# Sheet2.net
KiCad netlist of a schematic drawn in Altium Designer
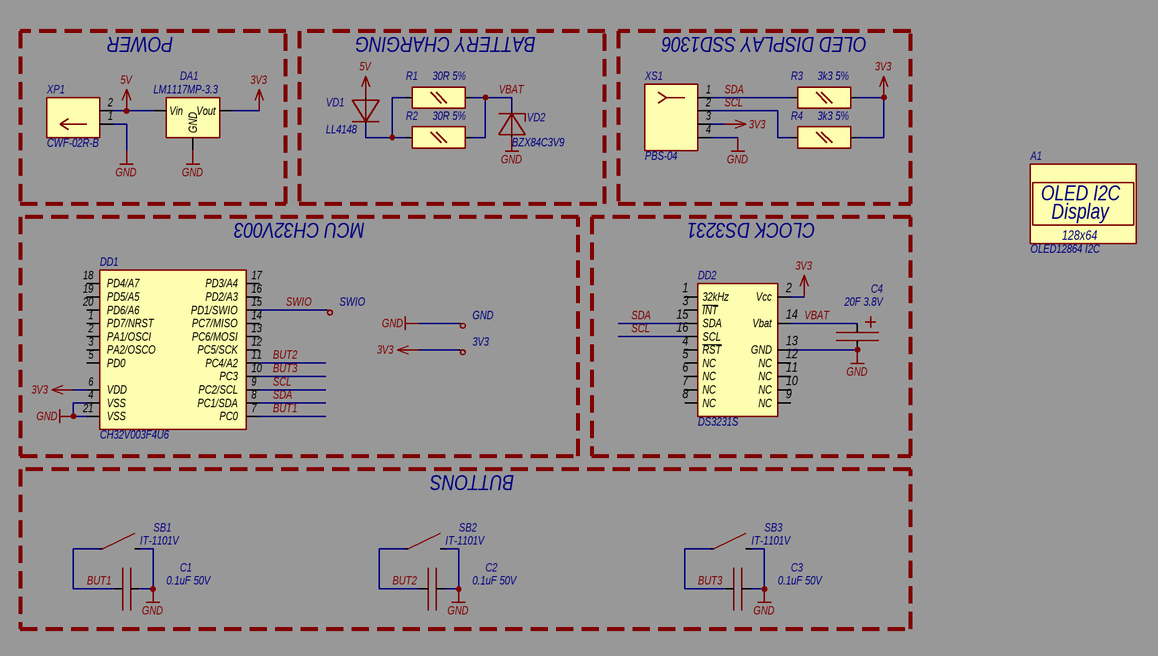
[diagram p0: Sheet2.SchDoc]

(export (version "E")
  (design (tool "Eeschema 10.0.6"))
  (components
    (comp (ref "A1")
      (value "OLED12864 I2C")
      (footprint "OLED12864 I2C connector")
      (fields (field (name "PART NUMBER") "OLED12864 I2C connector"))
      (libsource (lib "ATwiceDB") (part "OLED12864 I2C connector"))
    )
    (comp (ref "C1")
      (value "0.1uF 50V")
      (footprint "CAP SMD0805")
      (description "Конденсатор керамический SMD 0805 0.1uF 50V ±20%")
      (fields (field (name "PART NUMBER") "Cap 0805 0.1uF 50V"))
      (libsource (lib "ATwiceDB") (part "Cap"))
    )
    (comp (ref "C2")
      (value "0.1uF 50V")
      (footprint "CAP SMD0805")
      (description "Конденсатор керамический SMD 0805 0.1uF 50V ±20%")
      (fields (field (name "PART NUMBER") "Cap 0805 0.1uF 50V"))
      (libsource (lib "ATwiceDB") (part "Cap"))
    )
    (comp (ref "C3")
      (value "0.1uF 50V")
      (footprint "CAP SMD0805")
      (description "Конденсатор керамический SMD 0805 0.1uF 50V ±20%")
      (fields (field (name "PART NUMBER") "Cap 0805 0.1uF 50V"))
      (libsource (lib "ATwiceDB") (part "Cap"))
    )
    (comp (ref "C4")
      (value "20F 3.8V")
      (footprint "LIC0813LAYDOWN")
      (description "Ионистор 20F 3.8V 0813")
      (fields (field (name "PART NUMBER") "LIC 0813 206"))
      (libsource (lib "ATwiceDB") (part "Cap_plus"))
    )
    (comp (ref "DA1")
      (value "LM1117MP-3.3")
      (footprint "SOT223")
      (description "LDO стабилизатор")
      (libsource (lib "ATwiceDB") (part "LM1117"))
    )
    (comp (ref "DD1")
      (value "CH32V003F4U6")
      (footprint "QFN20_3X3_0.4")
      (description "Микроконтроллер CH32V003F4U6 QFN20 -40 +85")
      (libsource (lib "ATwiceDB") (part "CH32V003F4U6"))
    )
    (comp (ref "DD2")
      (value "DS3231S")
      (footprint "SO16W")
      (description "Микросхема DS3231S SO16W часы реального времени")
      (libsource (lib "ATwiceDB") (part "DS3231"))
    )
    (comp (ref "R1")
      (value "30R 5%")
      (footprint "SMD 0805")
      (description "Резистор SMD 0805 30R 5%")
      (fields (field (name "PART NUMBER") "Res 0805 30R 5%"))
      (libsource (lib "ATwiceDB") (part "Res_0125"))
    )
    (comp (ref "R2")
      (value "30R 5%")
      (footprint "SMD 0805")
      (description "Резистор SMD 0805 30R 5%")
      (fields (field (name "PART NUMBER") "Res 0805 30R 5%"))
      (libsource (lib "ATwiceDB") (part "Res_0125"))
    )
    (comp (ref "R3")
      (value "3k3 5%")
      (footprint "SMD 0805")
      (description "Резистор SMD 0805 3k3 5%")
      (fields (field (name "PART NUMBER") "Res 0805 3k3 5%"))
      (libsource (lib "ATwiceDB") (part "Res_0125"))
    )
    (comp (ref "R4")
      (value "3k3 5%")
      (footprint "SMD 0805")
      (description "Резистор SMD 0805 3k3 5%")
      (fields (field (name "PART NUMBER") "Res 0805 3k3 5%"))
      (libsource (lib "ATwiceDB") (part "Res_0125"))
    )
    (comp (ref "SB1")
      (value "IT-1101V")
      (footprint "IT-1101V_NO_SHIELD")
      (description "Кнопка тактовая IT-1101V угловая без рамки")
      (fields (field (name "PART NUMBER") "IT-1101V_no_shield"))
      (libsource (lib "ATwiceDB") (part "SB"))
    )
    (comp (ref "SB2")
      (value "IT-1101V")
      (footprint "IT-1101V_NO_SHIELD")
      (description "Кнопка тактовая IT-1101V угловая без рамки")
      (fields (field (name "PART NUMBER") "IT-1101V_no_shield"))
      (libsource (lib "ATwiceDB") (part "SB"))
    )
    (comp (ref "SB3")
      (value "IT-1101V")
      (footprint "IT-1101V_NO_SHIELD")
      (description "Кнопка тактовая IT-1101V угловая без рамки")
      (fields (field (name "PART NUMBER") "IT-1101V_no_shield"))
      (libsource (lib "ATwiceDB") (part "SB"))
    )
    (comp (ref "VD1")
      (value "LL4148")
      (footprint "MINIMELF")
      (description "Диод LL4148")
      (libsource (lib "ATwiceDB") (part "Diode"))
    )
    (comp (ref "VD2")
      (value "BZX84C3V9")
      (footprint "SOT23_1A3C")
      (description "Стабилитрон BZX84C3V9 SOT23")
      (libsource (lib "ATwiceDB") (part "Stab"))
    )
    (comp (ref "XP1")
      (value "CWF-02R-B")
      (footprint "CWF-02R-B")
      (description "Разъём CWF-02R-B вилка угловая 2,50мм тип B")
      (libsource (lib "ATwiceDB") (part "Conn_XP02"))
    )
    (comp (ref "XS1")
      (value "PBS-04")
      (footprint "PBS-04")
      (description "Разъём PBS-04 гнездо однорядное 2,54мм")
      (libsource (lib "ATwiceDB") (part "Conn_XS04"))
    )
    (comp (ref "XX1")
      (value "SWIO")
      (footprint "SMD_Pad")
      (fields (field (name "PART NUMBER") "SMD Pad"))
      (libsource (lib "ATwiceDB") (part "TestPoint"))
    )
    (comp (ref "XX2")
      (value "GND")
      (footprint "SMD_Pad")
      (fields (field (name "PART NUMBER") "SMD Pad"))
      (libsource (lib "ATwiceDB") (part "TestPoint"))
    )
    (comp (ref "XX3")
      (value "3V3")
      (footprint "SMD_Pad")
      (fields (field (name "PART NUMBER") "SMD Pad"))
      (libsource (lib "ATwiceDB") (part "TestPoint"))
    )
  )
  (nets
    (net (code "1") (name "/BUT1") (class "Default")
      (node (ref "C1") (pin "1") (pinfunction "1_1") (pintype "passive"))
      (node (ref "DD1") (pin "7") (pinfunction "PC0_7") (pintype "passive"))
      (node (ref "SB1") (pin "1") (pinfunction "1_1") (pintype "passive"))
    )
    (net (code "2") (name "/BUT2") (class "Default")
      (node (ref "C2") (pin "1") (pinfunction "1_1") (pintype "passive"))
      (node (ref "DD1") (pin "11") (pinfunction "PC4/A2_11") (pintype "passive"))
      (node (ref "SB2") (pin "1") (pinfunction "1_1") (pintype "passive"))
    )
    (net (code "3") (name "/BUT3") (class "Default")
      (node (ref "C3") (pin "1") (pinfunction "1_1") (pintype "passive"))
      (node (ref "DD1") (pin "10") (pinfunction "PC3_10") (pintype "passive"))
      (node (ref "SB3") (pin "1") (pinfunction "1_1") (pintype "passive"))
    )
    (net (code "4") (name "/SCL") (class "Default")
      (node (ref "DD1") (pin "9") (pinfunction "PC2/SCL_9") (pintype "passive"))
      (node (ref "DD2") (pin "16") (pinfunction "SCL_16") (pintype "passive"))
      (node (ref "R4") (pin "1") (pinfunction "1_1") (pintype "passive"))
      (node (ref "XS1") (pin "2") (pintype "passive"))
    )
    (net (code "5") (name "/SDA") (class "Default")
      (node (ref "DD1") (pin "8") (pinfunction "PC1/SDA_8") (pintype "passive"))
      (node (ref "DD2") (pin "15") (pinfunction "SDA_15") (pintype "passive"))
      (node (ref "R3") (pin "1") (pinfunction "1_1") (pintype "passive"))
      (node (ref "XS1") (pin "1") (pintype "passive"))
    )
    (net (code "6") (name "/SWIO") (class "Default")
      (node (ref "DD1") (pin "15") (pinfunction "PD1/SWIO_15") (pintype "passive"))
      (node (ref "XX1") (pin "1") (pinfunction "Name_1") (pintype "passive"))
    )
    (net (code "7") (name "/VBAT") (class "Default")
      (node (ref "C4") (pin "1") (pinfunction "1_1") (pintype "passive"))
      (node (ref "DD2") (pin "14") (pinfunction "Vbat_14") (pintype "passive"))
      (node (ref "R1") (pin "2") (pinfunction "2_2") (pintype "passive"))
      (node (ref "R2") (pin "2") (pinfunction "2_2") (pintype "passive"))
      (node (ref "VD2") (pin "C") (pinfunction "C_C") (pintype "passive"))
    )
    (net (code "8") (name "3V3") (class "Default")
      (node (ref "DA1") (pin "2") (pinfunction "Vout_2") (pintype "passive"))
      (node (ref "DD1") (pin "6") (pinfunction "VDD_6") (pintype "passive"))
      (node (ref "DD2") (pin "2") (pinfunction "Vcc_2") (pintype "passive"))
      (node (ref "R3") (pin "2") (pinfunction "2_2") (pintype "passive"))
      (node (ref "R4") (pin "2") (pinfunction "2_2") (pintype "passive"))
      (node (ref "XS1") (pin "3") (pintype "passive"))
      (node (ref "XX3") (pin "1") (pinfunction "Name_1") (pintype "passive"))
    )
    (net (code "9") (name "5V") (class "Default")
      (node (ref "DA1") (pin "3") (pinfunction "Vin_3") (pintype "passive"))
      (node (ref "VD1") (pin "A") (pinfunction "A_A") (pintype "passive"))
      (node (ref "XP1") (pin "2") (pintype "passive"))
    )
    (net (code "10") (name "GND") (class "Default")
      (node (ref "C1") (pin "2") (pinfunction "2_2") (pintype "passive"))
      (node (ref "C2") (pin "2") (pinfunction "2_2") (pintype "passive"))
      (node (ref "C3") (pin "2") (pinfunction "2_2") (pintype "passive"))
      (node (ref "C4") (pin "2") (pinfunction "2_2") (pintype "passive"))
      (node (ref "DA1") (pin "1") (pinfunction "GND_1") (pintype "passive"))
      (node (ref "DD1") (pin "21") (pinfunction "VSS_21") (pintype "passive"))
      (node (ref "DD1") (pin "4") (pinfunction "VSS_4") (pintype "passive"))
      (node (ref "DD2") (pin "13") (pinfunction "GND_13") (pintype "passive"))
      (node (ref "SB1") (pin "2") (pinfunction "2_2") (pintype "passive"))
      (node (ref "SB2") (pin "2") (pinfunction "2_2") (pintype "passive"))
      (node (ref "SB3") (pin "2") (pinfunction "2_2") (pintype "passive"))
      (node (ref "VD2") (pin "A") (pinfunction "A_A") (pintype "passive"))
      (node (ref "XP1") (pin "1") (pintype "passive"))
      (node (ref "XS1") (pin "4") (pintype "passive"))
      (node (ref "XX2") (pin "1") (pinfunction "Name_1") (pintype "passive"))
    )
    (net (code "11") (name "Net-(R1-Pad1)") (class "Default")
      (node (ref "R1") (pin "1") (pinfunction "1_1") (pintype "passive"))
      (node (ref "R2") (pin "1") (pinfunction "1_1") (pintype "passive"))
      (node (ref "VD1") (pin "C") (pinfunction "C_C") (pintype "passive"))
    )
    (net (code "12") (name "unconnected-(DD1-PA1{slash}OSCI-Pad2)") (class "Default")
      (node (ref "DD1") (pin "2") (pinfunction "PA1/OSCI_2") (pintype "passive"))
    )
    (net (code "13") (name "unconnected-(DD1-PA2{slash}OSCO-Pad3)") (class "Default")
      (node (ref "DD1") (pin "3") (pinfunction "PA2/OSCO_3") (pintype "passive"))
    )
    (net (code "14") (name "unconnected-(DD1-PC5{slash}SCK-Pad12)") (class "Default")
      (node (ref "DD1") (pin "12") (pinfunction "PC5/SCK_12") (pintype "passive"))
    )
    (net (code "15") (name "unconnected-(DD1-PC6{slash}MOSI-Pad13)") (class "Default")
      (node (ref "DD1") (pin "13") (pinfunction "PC6/MOSI_13") (pintype "passive"))
    )
    (net (code "16") (name "unconnected-(DD1-PC7{slash}MISO-Pad14)") (class "Default")
      (node (ref "DD1") (pin "14") (pinfunction "PC7/MISO_14") (pintype "passive"))
    )
    (net (code "17") (name "unconnected-(DD1-PD0-Pad5)") (class "Default")
      (node (ref "DD1") (pin "5") (pinfunction "PD0_5") (pintype "passive"))
    )
    (net (code "18") (name "unconnected-(DD1-PD2{slash}A3-Pad16)") (class "Default")
      (node (ref "DD1") (pin "16") (pinfunction "PD2/A3_16") (pintype "passive"))
    )
    (net (code "19") (name "unconnected-(DD1-PD3{slash}A4-Pad17)") (class "Default")
      (node (ref "DD1") (pin "17") (pinfunction "PD3/A4_17") (pintype "passive"))
    )
    (net (code "20") (name "unconnected-(DD1-PD4{slash}A7-Pad18)") (class "Default")
      (node (ref "DD1") (pin "18") (pinfunction "PD4/A7_18") (pintype "passive"))
    )
    (net (code "21") (name "unconnected-(DD1-PD5{slash}A5-Pad19)") (class "Default")
      (node (ref "DD1") (pin "19") (pinfunction "PD5/A5_19") (pintype "passive"))
    )
    (net (code "22") (name "unconnected-(DD1-PD6{slash}A6-Pad20)") (class "Default")
      (node (ref "DD1") (pin "20") (pinfunction "PD6/A6_20") (pintype "passive"))
    )
    (net (code "23") (name "unconnected-(DD1-PD7{slash}NRST-Pad1)") (class "Default")
      (node (ref "DD1") (pin "1") (pinfunction "PD7/NRST_1") (pintype "passive"))
    )
    (net (code "24") (name "unconnected-(DD2-32kHz-Pad1)") (class "Default")
      (node (ref "DD2") (pin "1") (pinfunction "32kHz_1") (pintype "passive"))
    )
    (net (code "25") (name "unconnected-(DD2-NC-Pad5)") (class "Default")
      (node (ref "DD2") (pin "5") (pinfunction "NC_5") (pintype "passive"))
    )
    (net (code "26") (name "unconnected-(DD2-NC-Pad6)") (class "Default")
      (node (ref "DD2") (pin "6") (pinfunction "NC_6") (pintype "passive"))
    )
    (net (code "27") (name "unconnected-(DD2-NC-Pad7)") (class "Default")
      (node (ref "DD2") (pin "7") (pinfunction "NC_7") (pintype "passive"))
    )
    (net (code "28") (name "unconnected-(DD2-NC-Pad8)") (class "Default")
      (node (ref "DD2") (pin "8") (pinfunction "NC_8") (pintype "passive"))
    )
    (net (code "29") (name "unconnected-(DD2-NC-Pad9)") (class "Default")
      (node (ref "DD2") (pin "9") (pinfunction "NC_9") (pintype "passive"))
    )
    (net (code "30") (name "unconnected-(DD2-NC-Pad10)") (class "Default")
      (node (ref "DD2") (pin "10") (pinfunction "NC_10") (pintype "passive"))
    )
    (net (code "31") (name "unconnected-(DD2-NC-Pad11)") (class "Default")
      (node (ref "DD2") (pin "11") (pinfunction "NC_11") (pintype "passive"))
    )
    (net (code "32") (name "unconnected-(DD2-NC-Pad12)") (class "Default")
      (node (ref "DD2") (pin "12") (pinfunction "NC_12") (pintype "passive"))
    )
    (net (code "33") (name "unconnected-(DD2-~{INT}-Pad3)") (class "Default")
      (node (ref "DD2") (pin "3") (pinfunction "~{INT}_3") (pintype "passive"))
    )
    (net (code "34") (name "unconnected-(DD2-~{RST}-Pad4)") (class "Default")
      (node (ref "DD2") (pin "4") (pinfunction "~{RST}_4") (pintype "passive"))
    )
  )
)
